# Nusbio_SPI_Extension.net
KiCad netlist of a schematic drawn in EAGLE
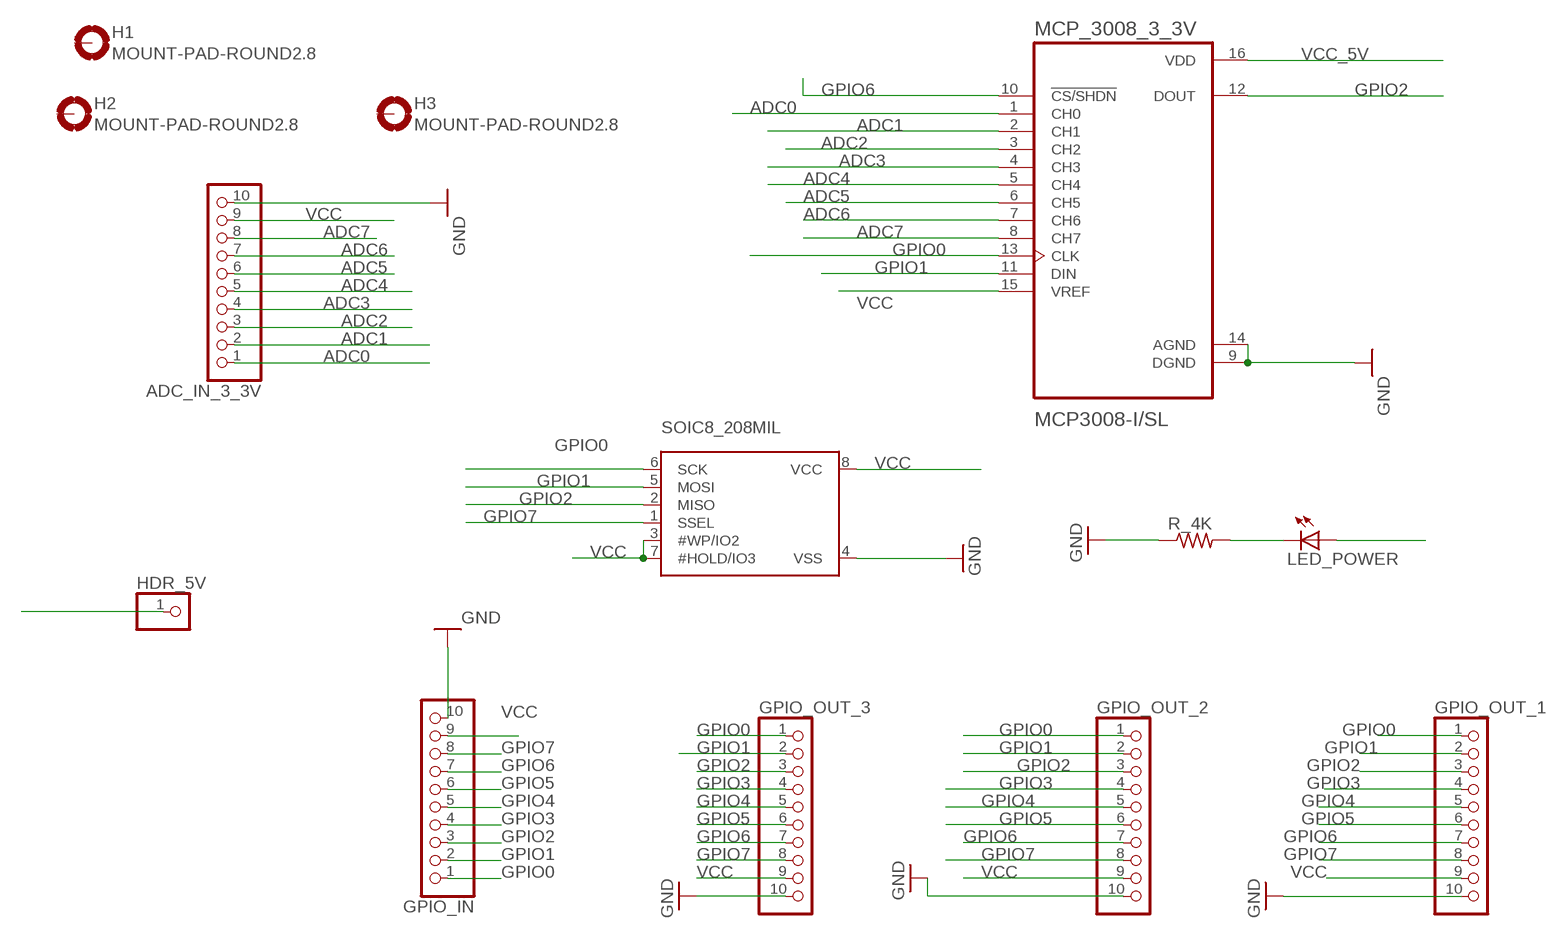
[diagram p0: schematic, sheet 1]

(export (version "E")
  (design (tool "Eeschema 10.0.6"))
  (components
    (comp (ref "ADC_IN_3_3V")
      (value "PINHD-1X10")
      (footprint "eagle-import:1X10-BIG")
      (libsource (lib "eagle-import") (part "PINHD-1X10"))
    )
    (comp (ref "GPIO_IN")
      (value "PINHD-1X10")
      (footprint "eagle-import:1X10-BIG")
      (libsource (lib "eagle-import") (part "PINHD-1X10"))
    )
    (comp (ref "GPIO_OUT_1")
      (value "PINHD-1X10")
      (footprint "eagle-import:1X10-BIG")
      (libsource (lib "eagle-import") (part "PINHD-1X10"))
    )
    (comp (ref "GPIO_OUT_2")
      (value "PINHD-1X10")
      (footprint "eagle-import:1X10-BIG")
      (libsource (lib "eagle-import") (part "PINHD-1X10"))
    )
    (comp (ref "GPIO_OUT_3")
      (value "PINHD-1X10")
      (footprint "eagle-import:1X10-BIG")
      (libsource (lib "eagle-import") (part "PINHD-1X10"))
    )
    (comp (ref "H1")
      (value "MOUNT-PAD-ROUND2.8")
      (footprint "eagle-import:2,8-PAD")
      (libsource (lib "eagle-import") (part "MOUNT-PAD-ROUND2.8"))
    )
    (comp (ref "H2")
      (value "MOUNT-PAD-ROUND2.8")
      (footprint "eagle-import:2,8-PAD")
      (libsource (lib "eagle-import") (part "MOUNT-PAD-ROUND2.8"))
    )
    (comp (ref "H3")
      (value "MOUNT-PAD-ROUND2.8")
      (footprint "eagle-import:2,8-PAD")
      (libsource (lib "eagle-import") (part "MOUNT-PAD-ROUND2.8"))
    )
    (comp (ref "HDR_5V")
      (value "PINHD-1X1")
      (footprint "eagle-import:1X01")
      (libsource (lib "eagle-import") (part "PINHD-1X1"))
    )
    (comp (ref "LED_POWER")
      (value "LEDSMT1206")
      (footprint "eagle-import:1206")
      (libsource (lib "eagle-import") (part "LEDSMT1206"))
    )
    (comp (ref "MCP_3008_3_3V")
      (value "MCP3008-I/SL")
      (footprint "eagle-import:SOIC127P600X175-16N")
      (fields (field (name "MF") "Microchip"))
      (libsource (lib "eagle-import") (part "MCP3008-I/SL"))
    )
    (comp (ref "R_4K")
      (value "R-US_R1206")
      (footprint "eagle-import:R1206")
      (libsource (lib "eagle-import") (part "R-US_R1206"))
    )
    (comp (ref "SOIC8_208MIL")
      (value "SPIFLASH_SOIC8208MIL")
      (footprint "eagle-import:SOIC8_208MIL")
      (libsource (lib "eagle-import") (part "SPIFLASH_SOIC8208MIL"))
    )
  )
  (nets
    (net (code "1") (name "/ADC0") (class "Default")
      (node (ref "ADC_IN_3_3V") (pin "1") (pinfunction "1_1") (pintype "passive"))
      (node (ref "MCP_3008_3_3V") (pin "1") (pinfunction "CH0_1") (pintype "input"))
    )
    (net (code "2") (name "/ADC1") (class "Default")
      (node (ref "ADC_IN_3_3V") (pin "2") (pinfunction "2_2") (pintype "passive"))
      (node (ref "MCP_3008_3_3V") (pin "2") (pinfunction "CH1_2") (pintype "input"))
    )
    (net (code "3") (name "/ADC2") (class "Default")
      (node (ref "ADC_IN_3_3V") (pin "3") (pinfunction "3_3") (pintype "passive"))
      (node (ref "MCP_3008_3_3V") (pin "3") (pinfunction "CH2_3") (pintype "input"))
    )
    (net (code "4") (name "/ADC3") (class "Default")
      (node (ref "ADC_IN_3_3V") (pin "4") (pinfunction "4_4") (pintype "passive"))
      (node (ref "MCP_3008_3_3V") (pin "4") (pinfunction "CH3_4") (pintype "input"))
    )
    (net (code "5") (name "/ADC4") (class "Default")
      (node (ref "ADC_IN_3_3V") (pin "5") (pinfunction "5_5") (pintype "passive"))
      (node (ref "MCP_3008_3_3V") (pin "5") (pinfunction "CH4_5") (pintype "input"))
    )
    (net (code "6") (name "/ADC5") (class "Default")
      (node (ref "ADC_IN_3_3V") (pin "6") (pinfunction "6_6") (pintype "passive"))
      (node (ref "MCP_3008_3_3V") (pin "6") (pinfunction "CH5_6") (pintype "input"))
    )
    (net (code "7") (name "/ADC6") (class "Default")
      (node (ref "ADC_IN_3_3V") (pin "7") (pinfunction "7_7") (pintype "passive"))
      (node (ref "MCP_3008_3_3V") (pin "7") (pinfunction "CH6_7") (pintype "input"))
    )
    (net (code "8") (name "/ADC7") (class "Default")
      (node (ref "ADC_IN_3_3V") (pin "8") (pinfunction "8_8") (pintype "passive"))
      (node (ref "MCP_3008_3_3V") (pin "8") (pinfunction "CH7_8") (pintype "input"))
    )
    (net (code "9") (name "/GPIO0") (class "Default")
      (node (ref "GPIO_IN") (pin "1") (pinfunction "1_1") (pintype "passive"))
      (node (ref "GPIO_OUT_1") (pin "1") (pinfunction "1_1") (pintype "passive"))
      (node (ref "GPIO_OUT_2") (pin "1") (pinfunction "1_1") (pintype "passive"))
      (node (ref "GPIO_OUT_3") (pin "1") (pinfunction "1_1") (pintype "passive"))
      (node (ref "MCP_3008_3_3V") (pin "13") (pinfunction "CLK_13") (pintype "input"))
      (node (ref "SOIC8_208MIL") (pin "6") (pinfunction "SCK_6") (pintype "bidirectional"))
    )
    (net (code "10") (name "/GPIO1") (class "Default")
      (node (ref "GPIO_IN") (pin "2") (pinfunction "2_2") (pintype "passive"))
      (node (ref "GPIO_OUT_1") (pin "2") (pinfunction "2_2") (pintype "passive"))
      (node (ref "GPIO_OUT_2") (pin "2") (pinfunction "2_2") (pintype "passive"))
      (node (ref "GPIO_OUT_3") (pin "2") (pinfunction "2_2") (pintype "passive"))
      (node (ref "MCP_3008_3_3V") (pin "11") (pinfunction "DIN_11") (pintype "input"))
      (node (ref "SOIC8_208MIL") (pin "5") (pinfunction "MOSI_5") (pintype "bidirectional"))
    )
    (net (code "11") (name "/GPIO2") (class "Default")
      (node (ref "GPIO_IN") (pin "3") (pinfunction "3_3") (pintype "passive"))
      (node (ref "GPIO_OUT_1") (pin "3") (pinfunction "3_3") (pintype "passive"))
      (node (ref "GPIO_OUT_2") (pin "3") (pinfunction "3_3") (pintype "passive"))
      (node (ref "GPIO_OUT_3") (pin "3") (pinfunction "3_3") (pintype "passive"))
      (node (ref "MCP_3008_3_3V") (pin "12") (pinfunction "DOUT_12") (pintype "output"))
      (node (ref "SOIC8_208MIL") (pin "2") (pinfunction "MISO_2") (pintype "bidirectional"))
    )
    (net (code "12") (name "/GPIO3") (class "Default")
      (node (ref "GPIO_IN") (pin "4") (pinfunction "4_4") (pintype "passive"))
      (node (ref "GPIO_OUT_1") (pin "4") (pinfunction "4_4") (pintype "passive"))
      (node (ref "GPIO_OUT_2") (pin "4") (pinfunction "4_4") (pintype "passive"))
      (node (ref "GPIO_OUT_3") (pin "4") (pinfunction "4_4") (pintype "passive"))
    )
    (net (code "13") (name "/GPIO4") (class "Default")
      (node (ref "GPIO_IN") (pin "5") (pinfunction "5_5") (pintype "passive"))
      (node (ref "GPIO_OUT_1") (pin "5") (pinfunction "5_5") (pintype "passive"))
      (node (ref "GPIO_OUT_2") (pin "5") (pinfunction "5_5") (pintype "passive"))
      (node (ref "GPIO_OUT_3") (pin "5") (pinfunction "5_5") (pintype "passive"))
    )
    (net (code "14") (name "/GPIO5") (class "Default")
      (node (ref "GPIO_IN") (pin "6") (pinfunction "6_6") (pintype "passive"))
      (node (ref "GPIO_OUT_1") (pin "6") (pinfunction "6_6") (pintype "passive"))
      (node (ref "GPIO_OUT_2") (pin "6") (pinfunction "6_6") (pintype "passive"))
      (node (ref "GPIO_OUT_3") (pin "6") (pinfunction "6_6") (pintype "passive"))
    )
    (net (code "15") (name "/GPIO6") (class "Default")
      (node (ref "GPIO_IN") (pin "7") (pinfunction "7_7") (pintype "passive"))
      (node (ref "GPIO_OUT_1") (pin "7") (pinfunction "7_7") (pintype "passive"))
      (node (ref "GPIO_OUT_2") (pin "7") (pinfunction "7_7") (pintype "passive"))
      (node (ref "GPIO_OUT_3") (pin "7") (pinfunction "7_7") (pintype "passive"))
      (node (ref "MCP_3008_3_3V") (pin "10") (pinfunction "~{CS/SHDN}_10") (pintype "input"))
    )
    (net (code "16") (name "/GPIO7") (class "Default")
      (node (ref "GPIO_IN") (pin "8") (pinfunction "8_8") (pintype "passive"))
      (node (ref "GPIO_OUT_1") (pin "8") (pinfunction "8_8") (pintype "passive"))
      (node (ref "GPIO_OUT_2") (pin "8") (pinfunction "8_8") (pintype "passive"))
      (node (ref "GPIO_OUT_3") (pin "8") (pinfunction "8_8") (pintype "passive"))
      (node (ref "SOIC8_208MIL") (pin "1") (pinfunction "SSEL_1") (pintype "bidirectional"))
    )
    (net (code "17") (name "/VCC") (class "Default")
      (node (ref "ADC_IN_3_3V") (pin "9") (pinfunction "9_9") (pintype "passive"))
      (node (ref "GPIO_IN") (pin "9") (pinfunction "9_9") (pintype "passive"))
      (node (ref "GPIO_OUT_1") (pin "9") (pinfunction "9_9") (pintype "passive"))
      (node (ref "GPIO_OUT_2") (pin "9") (pinfunction "9_9") (pintype "passive"))
      (node (ref "GPIO_OUT_3") (pin "9") (pinfunction "9_9") (pintype "passive"))
      (node (ref "LED_POWER") (pin "A") (pinfunction "A_A") (pintype "passive"))
      (node (ref "MCP_3008_3_3V") (pin "15") (pinfunction "VREF_15") (pintype "input"))
      (node (ref "SOIC8_208MIL") (pin "3") (pinfunction "#WP/IO2_3") (pintype "bidirectional"))
      (node (ref "SOIC8_208MIL") (pin "7") (pinfunction "#HOLD/IO3_7") (pintype "bidirectional"))
      (node (ref "SOIC8_208MIL") (pin "8") (pinfunction "VCC_8") (pintype "bidirectional"))
    )
    (net (code "18") (name "/VCC_5V") (class "Default")
      (node (ref "HDR_5V") (pin "1") (pinfunction "1_1") (pintype "passive"))
      (node (ref "MCP_3008_3_3V") (pin "16") (pinfunction "VDD_16") (pintype "power_in"))
    )
    (net (code "19") (name "GND") (class "Default")
      (node (ref "ADC_IN_3_3V") (pin "10") (pinfunction "10_10") (pintype "passive"))
      (node (ref "GPIO_IN") (pin "10") (pinfunction "10_10") (pintype "passive"))
      (node (ref "GPIO_OUT_1") (pin "10") (pinfunction "10_10") (pintype "passive"))
      (node (ref "GPIO_OUT_2") (pin "10") (pinfunction "10_10") (pintype "passive"))
      (node (ref "GPIO_OUT_3") (pin "10") (pinfunction "10_10") (pintype "passive"))
      (node (ref "MCP_3008_3_3V") (pin "14") (pinfunction "AGND_14") (pintype "power_in"))
      (node (ref "MCP_3008_3_3V") (pin "9") (pinfunction "DGND_9") (pintype "power_in"))
      (node (ref "R_4K") (pin "1") (pinfunction "1_1") (pintype "passive"))
      (node (ref "SOIC8_208MIL") (pin "4") (pinfunction "VSS_4") (pintype "bidirectional"))
    )
    (net (code "20") (name "Net-(LED_POWER-PadC)") (class "Default")
      (node (ref "LED_POWER") (pin "C") (pinfunction "C_C") (pintype "passive"))
      (node (ref "R_4K") (pin "2") (pinfunction "2_2") (pintype "passive"))
    )
    (net (code "21") (name "unconnected-(H1-MOUNT-PadB2,8)") (class "Default")
      (node (ref "H1") (pin "B2,8") (pinfunction "MOUNT_B2,8") (pintype "passive"))
    )
    (net (code "22") (name "unconnected-(H2-MOUNT-PadB2,8)") (class "Default")
      (node (ref "H2") (pin "B2,8") (pinfunction "MOUNT_B2,8") (pintype "passive"))
    )
    (net (code "23") (name "unconnected-(H3-MOUNT-PadB2,8)") (class "Default")
      (node (ref "H3") (pin "B2,8") (pinfunction "MOUNT_B2,8") (pintype "passive"))
    )
  )
)
